# Ethernet1_PoE.net
KiCad netlist of a schematic drawn in Altium Designer
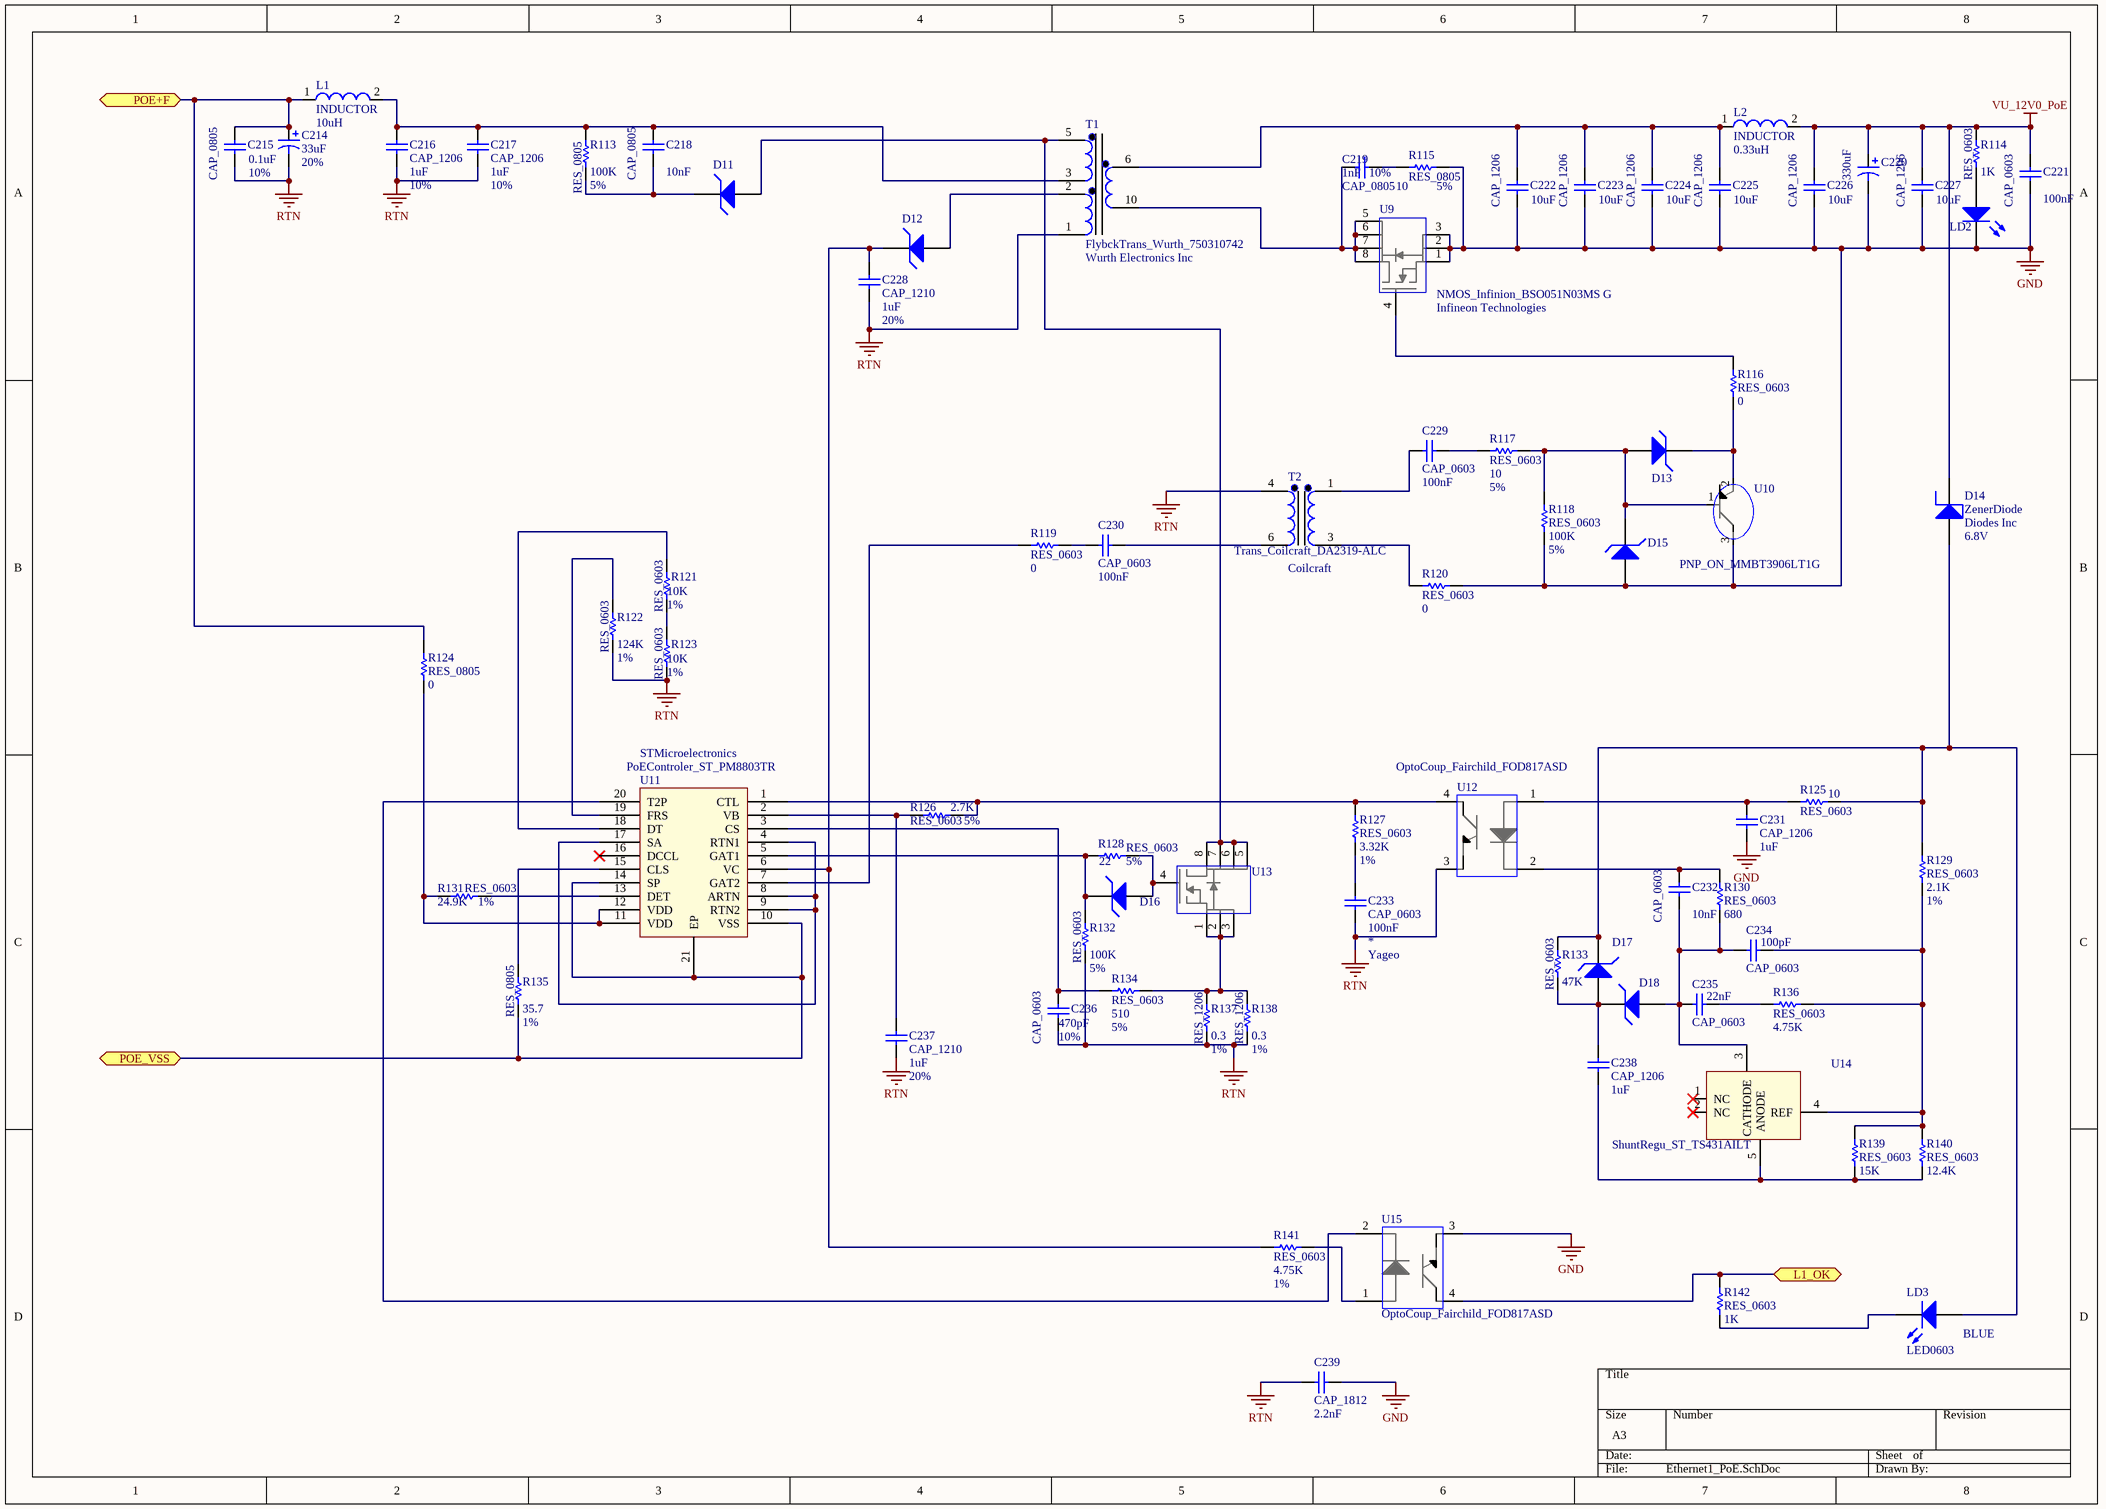
[diagram p0: Ethernet1_PoE.SchDoc]

(export (version "E")
  (design (tool "Eeschema 10.0.6"))
  (components
    (comp (ref "C214")
      (value "33uF")
      (footprint "CapPol_Al_EEE-2AA330P")
      (description "CAP ALUM 33UF 100V 20% SMD")
      (fields
        (field (name "TOLERANCE") "20%")
        (field (name "PART NUMBER") "EEE-2AA330P")
        (field (name "MANUFACTURER") "Panasonic Electronic Components")
      )
      (libsource (lib "COMRAD_Database") (part "Cap Pol1"))
    )
    (comp (ref "C215")
      (value "CAP_0805")
      (footprint "CAPC0805(2012)75_N")
      (description "CAP CER 0.1UF 100V 10% X7R 0805")
      (fields
        (field (name "ALTIUM_VALUE") "0.1uF")
        (field (name "TOLERANCE") "10%")
        (field (name "PART NUMBER") "C2012X7R2A104K")
        (field (name "MANUFACTURER") "TDK Corporation")
      )
      (libsource (lib "COMRAD_Database") (part "CAP_0805"))
    )
    (comp (ref "C216")
      (value "CAP_1206")
      (footprint "CAPC1206(3216)100_N")
      (description "CAP CER 1UF 100V 10% X7R 1206")
      (fields
        (field (name "ALTIUM_VALUE") "1uF")
        (field (name "TOLERANCE") "10%")
        (field (name "PART NUMBER") "C3216X7R2A105K")
        (field (name "MANUFACTURER") "TDK Corporation")
      )
      (libsource (lib "COMRAD_Database") (part "CAP_1206"))
    )
    (comp (ref "C217")
      (value "CAP_1206")
      (footprint "CAPC1206(3216)100_N")
      (description "CAP CER 1UF 100V 10% X7R 1206")
      (fields
        (field (name "ALTIUM_VALUE") "1uF")
        (field (name "TOLERANCE") "10%")
        (field (name "PART NUMBER") "C3216X7R2A105K")
        (field (name "MANUFACTURER") "TDK Corporation")
      )
      (libsource (lib "COMRAD_Database") (part "CAP_1206"))
    )
    (comp (ref "C218")
      (value "CAP_0805")
      (footprint "CAPC0805(2012)75_N")
      (description "CAP CER 10000PF 100V X7R 0805")
      (fields
        (field (name "ALTIUM_VALUE") "10nF")
        (field (name "PART NUMBER") "C2012X7R2A103K")
        (field (name "MANUFACTURER") "TDK Corporation")
      )
      (libsource (lib "COMRAD_Database") (part "CAP_0805"))
    )
    (comp (ref "C219")
      (value "CAP_0805")
      (footprint "CAPC0805(2012)75_N")
      (description "CAP CER 1000PF 100V 10% X7R 0805")
      (fields
        (field (name "ALTIUM_VALUE") "1nF")
        (field (name "TOLERANCE") "10%")
        (field (name "PART NUMBER") "101R15W102KV4T")
        (field (name "MANUFACTURER") "Johanson Dielectrics Inc")
      )
      (libsource (lib "COMRAD_Database") (part "CAP_0805"))
    )
    (comp (ref "C220")
      (value "330uF")
      (footprint "CapPol_Al_PCV1D331MCL2GS")
      (description "CAP ALUM 330UF 20V 20% SMD")
      (fields (field (name "PART NUMBER") "PCV1D331MCL2GS") (field (name "MANUFACTURER") "Nichicon"))
      (libsource (lib "COMRAD_Database") (part "Cap Pol1"))
    )
    (comp (ref "C221")
      (value "CAP_0603")
      (footprint "CAPC0603(1608)100_N:CAPC0603(1608)100_N")
      (description "CAP CER 0.1UF 50V Y5V 0603")
      (fields
        (field (name "ALTIUM_VALUE") "100nF")
        (field (name "PART NUMBER") "CC0603ZRY5V9BB104")
        (field (name "MANUFACTURER") "Yageo")
      )
      (libsource (lib "COMRAD_Database") (part "CAP_0603"))
    )
    (comp (ref "C222")
      (value "CAP_1206")
      (footprint "CAPC1206(3216)100_N")
      (description "CAP CER 10UF 25V Y5V 1206")
      (fields
        (field (name "ALTIUM_VALUE") "10uF")
        (field (name "PART NUMBER") "TMK316F106ZL-T")
        (field (name "MANUFACTURER") "Taiyo Yuden")
      )
      (libsource (lib "COMRAD_Database") (part "CAP_1206"))
    )
    (comp (ref "C223")
      (value "CAP_1206")
      (footprint "CAPC1206(3216)100_N")
      (description "CAP CER 10UF 25V Y5V 1206")
      (fields
        (field (name "ALTIUM_VALUE") "10uF")
        (field (name "PART NUMBER") "TMK316F106ZL-T")
        (field (name "MANUFACTURER") "Taiyo Yuden")
      )
      (libsource (lib "COMRAD_Database") (part "CAP_1206"))
    )
    (comp (ref "C224")
      (value "CAP_1206")
      (footprint "CAPC1206(3216)100_N")
      (description "CAP CER 10UF 25V Y5V 1206")
      (fields
        (field (name "ALTIUM_VALUE") "10uF")
        (field (name "PART NUMBER") "TMK316F106ZL-T")
        (field (name "MANUFACTURER") "Taiyo Yuden")
      )
      (libsource (lib "COMRAD_Database") (part "CAP_1206"))
    )
    (comp (ref "C225")
      (value "CAP_1206")
      (footprint "CAPC1206(3216)100_N")
      (description "CAP CER 10UF 25V Y5V 1206")
      (fields
        (field (name "ALTIUM_VALUE") "10uF")
        (field (name "PART NUMBER") "TMK316F106ZL-T")
        (field (name "MANUFACTURER") "Taiyo Yuden")
      )
      (libsource (lib "COMRAD_Database") (part "CAP_1206"))
    )
    (comp (ref "C226")
      (value "CAP_1206")
      (footprint "CAPC1206(3216)100_N")
      (description "CAP CER 10UF 25V Y5V 1206")
      (fields
        (field (name "ALTIUM_VALUE") "10uF")
        (field (name "PART NUMBER") "TMK316F106ZL-T")
        (field (name "MANUFACTURER") "Taiyo Yuden")
      )
      (libsource (lib "COMRAD_Database") (part "CAP_1206"))
    )
    (comp (ref "C227")
      (value "CAP_1206")
      (footprint "CAPC1206(3216)100_N")
      (description "CAP CER 10UF 25V Y5V 1206")
      (fields
        (field (name "ALTIUM_VALUE") "10uF")
        (field (name "PART NUMBER") "TMK316F106ZL-T")
        (field (name "MANUFACTURER") "Taiyo Yuden")
      )
      (libsource (lib "COMRAD_Database") (part "CAP_1206"))
    )
    (comp (ref "C228")
      (value "CAP_1210")
      (footprint "CAPC1210(3225)100_N")
      (description "CAP CER 1UF 16V 20% X7R 1210")
      (fields
        (field (name "ALTIUM_VALUE") "1uF")
        (field (name "TOLERANCE") "20%")
        (field (name "PART NUMBER") "160X41W105MV4E")
        (field (name "MANUFACTURER") "Johanson Dielectrics Inc")
      )
      (libsource (lib "COMRAD_Database") (part "CAP_1210"))
    )
    (comp (ref "C229")
      (value "CAP_0603")
      (footprint "CAPC0603(1608)100_N:CAPC0603(1608)100_N")
      (description "CAP CER 0.1UF 50V Y5V 0603")
      (fields
        (field (name "ALTIUM_VALUE") "100nF")
        (field (name "PART NUMBER") "CC0603ZRY5V9BB104")
        (field (name "MANUFACTURER") "Yageo")
      )
      (libsource (lib "COMRAD_Database") (part "CAP_0603"))
    )
    (comp (ref "C230")
      (value "CAP_0603")
      (footprint "CAPC0603(1608)100_N:CAPC0603(1608)100_N")
      (description "CAP CER 0.1UF 50V Y5V 0603")
      (fields
        (field (name "ALTIUM_VALUE") "100nF")
        (field (name "PART NUMBER") "CC0603ZRY5V9BB104")
        (field (name "MANUFACTURER") "Yageo")
      )
      (libsource (lib "COMRAD_Database") (part "CAP_0603"))
    )
    (comp (ref "C231")
      (value "CAP_1206")
      (footprint "CAPC1206(3216)100_N")
      (description "CAP CER 1UF 100V 10% X7R 1206")
      (fields
        (field (name "ALTIUM_VALUE") "1uF")
        (field (name "PART NUMBER") "C3216X7R2A105K")
        (field (name "MANUFACTURER") "TDK Corporation")
      )
      (libsource (lib "COMRAD_Database") (part "CAP_1206"))
    )
    (comp (ref "C232")
      (value "CAP_0603")
      (footprint "CAPC0603(1608)100_N:CAPC0603(1608)100_N")
      (description "CAP CER 10000PF 50V 10% X7R 0603")
      (fields
        (field (name "ALTIUM_VALUE") "10nF")
        (field (name "PART NUMBER") "C0603C103K5RACTU")
        (field (name "MANUFACTURER") "Kemet")
      )
      (libsource (lib "COMRAD_Database") (part "CAP_0603"))
    )
    (comp (ref "C233")
      (value "CAP_0603")
      (footprint "CAPC0603(1608)100_N:CAPC0603(1608)100_N")
      (description "CAP CER 0.1UF 50V Y5V 0603")
      (fields
        (field (name "ALTIUM_VALUE") "100nF")
        (field (name "TOLERANCE") "*")
        (field (name "PART NUMBER") "CC0603ZRY5V9BB104")
        (field (name "MANUFACTURER") "Yageo")
      )
      (libsource (lib "COMRAD_Database") (part "CAP_0603"))
    )
    (comp (ref "C234")
      (value "CAP_0603")
      (footprint "CAPC0603(1608)100_N:CAPC0603(1608)100_N")
      (description "CAP CER 100PF 50V 5% NP0 0603")
      (fields
        (field (name "ALTIUM_VALUE") "100pF")
        (field (name "PART NUMBER") "C0603C101J5GACTU")
        (field (name "MANUFACTURER") "Kemet")
      )
      (libsource (lib "COMRAD_Database") (part "CAP_0603"))
    )
    (comp (ref "C235")
      (value "CAP_0603")
      (footprint "CAPC0603(1608)100_N:CAPC0603(1608)100_N")
      (description "CAP CER 0.022UF 50V 10% X7R 0603")
      (fields
        (field (name "ALTIUM_VALUE") "22nF")
        (field (name "PART NUMBER") "C0603C223K5RACTU")
        (field (name "MANUFACTURER") "Kemet")
      )
      (libsource (lib "COMRAD_Database") (part "CAP_0603"))
    )
    (comp (ref "C236")
      (value "CAP_0603")
      (footprint "CAPC0603(1608)100_N:CAPC0603(1608)100_N")
      (description "CAP CER 470PF 50V 10% X7R 0603")
      (fields
        (field (name "ALTIUM_VALUE") "470pF")
        (field (name "TOLERANCE") "10%")
        (field (name "PART NUMBER") "CC0603KRX7R9BB471")
        (field (name "MANUFACTURER") "Yageo")
      )
      (libsource (lib "COMRAD_Database") (part "CAP_0603"))
    )
    (comp (ref "C237")
      (value "CAP_1210")
      (footprint "CAPC1210(3225)100_N")
      (description "CAP CER 1UF 16V 20% X7R 1210")
      (fields
        (field (name "ALTIUM_VALUE") "1uF")
        (field (name "TOLERANCE") "20%")
        (field (name "PART NUMBER") "160X41W105MV4E")
        (field (name "MANUFACTURER") "Johanson Dielectrics Inc")
      )
      (libsource (lib "COMRAD_Database") (part "CAP_1210"))
    )
    (comp (ref "C238")
      (value "CAP_1206")
      (footprint "CAPC1206(3216)100_N")
      (description "CAP CER 1UF 100V 10% X7R 1206")
      (fields
        (field (name "ALTIUM_VALUE") "1uF")
        (field (name "PART NUMBER") "C3216X7R2A105K")
        (field (name "MANUFACTURER") "TDK Corporation")
      )
      (libsource (lib "COMRAD_Database") (part "CAP_1206"))
    )
    (comp (ref "C239")
      (value "CAP_1812")
      (footprint "CAPC1812(4532)250_N")
      (description "CAP CER 2200PF 2KV 10% X7R 1812")
      (fields
        (field (name "ALTIUM_VALUE") "2.2nF")
        (field (name "PART NUMBER") "C1812C222KGRACTU")
        (field (name "MANUFACTURER") "Kemet")
      )
      (libsource (lib "COMRAD_Database") (part "CAP_1812"))
    )
    (comp (ref "D11")
      (value "Shottky Diode")
      (footprint "SchottlyDiode_STPS2H100A_SMA")
      (description "DIODE SCHOTTKY PWR 100V 2A SMA")
      (fields (field (name "PART NUMBER") "STPS2H100A") (field (name "MANUFACTURER") "STMicroelectronics"))
      (libsource (lib "COMRAD_Database") (part "ShottkyDiode"))
    )
    (comp (ref "D12")
      (value "Shottky Diode")
      (footprint "SchottkyDiode_BAT46JFILM")
      (description "IC DIODE SCHOTTKY SS SOD-323")
      (fields (field (name "PART NUMBER") "BAT46JFILM") (field (name "MANUFACTURER") "STMicroelectronics"))
      (libsource (lib "COMRAD_Database") (part "ShottkyDiode"))
    )
    (comp (ref "D13")
      (value "Shottky Diode")
      (footprint "SchottkyDiode_BAT46JFILM")
      (description "IC DIODE SCHOTTKY SS SOD-323")
      (fields (field (name "PART NUMBER") "BAT46JFILM") (field (name "MANUFACTURER") "STMicroelectronics"))
      (libsource (lib "COMRAD_Database") (part "ShottkyDiode"))
    )
    (comp (ref "D14")
      (value "ZenerDiode")
      (footprint "ZenerDiode_DDZ6V8CSF-7_2-PIN")
      (description "DIODE ZENER 6.84V 500MW SOD323F")
      (fields
        (field (name "PART NUMBER") "DDZ6V8CSF-7")
        (field (name "MANUFACTURER") "Diodes Inc")
        (field (name "ALTIUM_VALUE") "6.8V")
      )
      (libsource (lib "COMRAD_Database") (part "ZenerDiode"))
    )
    (comp (ref "D15")
      (value "Shottky Diode")
      (footprint "SchottkyDiode_BAT46JFILM")
      (description "IC DIODE SCHOTTKY SS SOD-323")
      (fields (field (name "PART NUMBER") "BAT46JFILM") (field (name "MANUFACTURER") "STMicroelectronics"))
      (libsource (lib "COMRAD_Database") (part "ShottkyDiode"))
    )
    (comp (ref "D16")
      (value "Shottky Diode")
      (footprint "SchottkyDiode_BAT46JFILM")
      (description "IC DIODE SCHOTTKY SS SOD-323")
      (fields (field (name "PART NUMBER") "BAT46JFILM") (field (name "MANUFACTURER") "STMicroelectronics"))
      (libsource (lib "COMRAD_Database") (part "ShottkyDiode"))
    )
    (comp (ref "D17")
      (value "Shottky Diode")
      (footprint "SchottkyDiode_BAT46JFILM")
      (description "IC DIODE SCHOTTKY SS SOD-323")
      (fields (field (name "PART NUMBER") "BAT46JFILM") (field (name "MANUFACTURER") "STMicroelectronics"))
      (libsource (lib "COMRAD_Database") (part "ShottkyDiode"))
    )
    (comp (ref "D18")
      (value "Shottky Diode")
      (footprint "SchottkyDiode_BAT46JFILM")
      (description "IC DIODE SCHOTTKY SS SOD-323")
      (fields (field (name "PART NUMBER") "BAT46JFILM") (field (name "MANUFACTURER") "STMicroelectronics"))
      (libsource (lib "COMRAD_Database") (part "ShottkyDiode"))
    )
    (comp (ref "L1")
      (value "INDUCTOR")
      (footprint "Inductor_MSS7341-103MLB_2-PIN")
      (description "INDUCTOR, 10uH,DCR 0.038, CURRENT 1.64A")
      (fields
        (field (name "ALTIUM_VALUE") "10uH")
        (field (name "PART NUMBER") "MSS7341-103MLB")
        (field (name "MANUFACTURER") "Coilcraft")
      )
      (libsource (lib "COMRAD_Database") (part "SYM-0029-00001-1"))
    )
    (comp (ref "L2")
      (value "INDUCTOR")
      (footprint "Inductor_DO1813H-181MLB_2-PINS")
      (description "INDUCTOR, 0.33uH,DCR 0.004, CURRENT 10A")
      (fields
        (field (name "ALTIUM_VALUE") "0.33uH")
        (field (name "PART NUMBER") "DO1813H-181MLB")
        (field (name "MANUFACTURER") "Coilcraft")
      )
      (libsource (lib "COMRAD_Database") (part "SYM-0029-00001-1"))
    )
    (comp (ref "LD2")
      (value "LED0805")
      (footprint "LED0805(2012):LED0805(2012)")
      (description "LED GREEN CLEAR THIN 0805 SMD")
      (fields (field (name "PART NUMBER") "LTST-C171GKT") (field (name "MANUFACTURER") "Lite-On Inc"))
      (libsource (lib "COMRAD_Database") (part "LED0805"))
    )
    (comp (ref "LD3")
      (value "LED0603")
      (footprint "LED0603(1608):LED0603(1608)")
      (description "Blue, SMD, 0603 Hi Brite")
      (fields
        (field (name "PART NUMBER") "UT-692NB")
        (field (name "MANUFACTURER") "LightComp LED")
        (field (name "ALTIUM_VALUE") "BLUE")
      )
      (libsource (lib "COMRAD_Database") (part "LED0603"))
    )
    (comp (ref "R113")
      (value "RES_0805")
      (footprint "RESC0805(2012)_N")
      (description "RES 100K OHM 1/8W 5% 0805 SMD")
      (fields
        (field (name "ALTIUM_VALUE") "100K")
        (field (name "TOLERANCE") "5%")
        (field (name "PART NUMBER") "CRCW0805100KJNEA")
        (field (name "MANUFACTURER") "Vishay Dale")
      )
      (libsource (lib "COMRAD_Database") (part "RES_0805"))
    )
    (comp (ref "R114")
      (value "RES_0603")
      (footprint "RESC0603(1608)_N")
      (description "RES 1.0K OHM 1/10W 5% 0603 SMD")
      (fields
        (field (name "ALTIUM_VALUE") "1K")
        (field (name "PART NUMBER") "ERJ-3GEYJ102V")
        (field (name "MANUFACTURER") "Panasonic Electronic Components")
      )
      (libsource (lib "COMRAD_Database") (part "RES_0603"))
    )
    (comp (ref "R115")
      (value "RES_0805")
      (footprint "RESC0805(2012)_N")
      (description "RES 10 OHM 1/8W 5% 0805 SMD")
      (fields
        (field (name "ALTIUM_VALUE") "10")
        (field (name "TOLERANCE") "5%")
        (field (name "PART NUMBER") "CRCW080510R0JNEA")
        (field (name "MANUFACTURER") "Vishay Dale")
      )
      (libsource (lib "COMRAD_Database") (part "RES_0805"))
    )
    (comp (ref "R116")
      (value "RES_0603")
      (footprint "RESC0603(1608)_N")
      (description "RES 0.0 OHM 1/10W 0603 SMD")
      (fields
        (field (name "ALTIUM_VALUE") "0")
        (field (name "PART NUMBER") "ERJ-3GEY0R00V")
        (field (name "MANUFACTURER") "Panasonic Electronic Components")
      )
      (libsource (lib "COMRAD_Database") (part "RES_0603"))
    )
    (comp (ref "R117")
      (value "RES_0603")
      (footprint "RESC0603(1608)_N")
      (description "RES 10 OHM 1/10W 5% 0603 SMD")
      (fields
        (field (name "ALTIUM_VALUE") "10")
        (field (name "TOLERANCE") "5%")
        (field (name "PART NUMBER") "ERJ-3GEYJ100V")
        (field (name "MANUFACTURER") "Panasonic Electronic Components")
      )
      (libsource (lib "COMRAD_Database") (part "RES_0603"))
    )
    (comp (ref "R118")
      (value "RES_0603")
      (footprint "RESC0603(1608)_N")
      (description "RES 100K OHM 1/10W 5% 0603 SMD")
      (fields
        (field (name "ALTIUM_VALUE") "100K")
        (field (name "TOLERANCE") "5%")
        (field (name "PART NUMBER") "ERJ-3GEYJ104V")
        (field (name "MANUFACTURER") "Panasonic Electronic Components")
      )
      (libsource (lib "COMRAD_Database") (part "RES_0603"))
    )
    (comp (ref "R119")
      (value "RES_0603")
      (footprint "RESC0603(1608)_N")
      (description "RES 0.0 OHM 1/10W 0603 SMD")
      (fields
        (field (name "ALTIUM_VALUE") "0")
        (field (name "PART NUMBER") "ERJ-3GEY0R00V")
        (field (name "MANUFACTURER") "Panasonic Electronic Components")
      )
      (libsource (lib "COMRAD_Database") (part "RES_0603"))
    )
    (comp (ref "R120")
      (value "RES_0603")
      (footprint "RESC0603(1608)_N")
      (description "RES 0.0 OHM 1/10W 0603 SMD")
      (fields
        (field (name "ALTIUM_VALUE") "0")
        (field (name "PART NUMBER") "ERJ-3GEY0R00V")
        (field (name "MANUFACTURER") "Panasonic Electronic Components")
      )
      (libsource (lib "COMRAD_Database") (part "RES_0603"))
    )
    (comp (ref "R121")
      (value "RES_0603")
      (footprint "RESC0603(1608)_N")
      (description "RES 10.0K OHM 1/10W 1% 0603 SMD")
      (fields
        (field (name "ALTIUM_VALUE") "10K")
        (field (name "TOLERANCE") "1%")
        (field (name "PART NUMBER") "ERJ-3EKF1002V")
        (field (name "MANUFACTURER") "Panasonic Electronics Components")
      )
      (libsource (lib "COMRAD_Database") (part "RES_0603"))
    )
    (comp (ref "R122")
      (value "RES_0603")
      (footprint "RESC0603(1608)_N")
      (description "RES 124K OHM 1/10W 1% 0603 SMD")
      (fields
        (field (name "ALTIUM_VALUE") "124K")
        (field (name "TOLERANCE") "1%")
        (field (name "PART NUMBER") "ERJ-3EKF1243V")
        (field (name "MANUFACTURER") "Panasonic Electronic Components")
      )
      (libsource (lib "COMRAD_Database") (part "RES_0603"))
    )
    (comp (ref "R123")
      (value "RES_0603")
      (footprint "RESC0603(1608)_N")
      (description "RES 10.0K OHM 1/10W 1% 0603 SMD")
      (fields
        (field (name "ALTIUM_VALUE") "10K")
        (field (name "TOLERANCE") "1%")
        (field (name "PART NUMBER") "ERJ-3EKF1002V")
        (field (name "MANUFACTURER") "Panasonic Electronics Components")
      )
      (libsource (lib "COMRAD_Database") (part "RES_0603"))
    )
    (comp (ref "R124")
      (value "RES_0805")
      (footprint "RESC0805(2012)_N")
      (description "RES 0.0 OHM 1/8W 0805 SMD")
      (fields
        (field (name "ALTIUM_VALUE") "0")
        (field (name "PART NUMBER") "CRCW08050000Z0EA")
        (field (name "MANUFACTURER") "Vishay Dale")
      )
      (libsource (lib "COMRAD_Database") (part "RES_0805"))
    )
    (comp (ref "R125")
      (value "RES_0603")
      (footprint "RESC0603(1608)_N")
      (description "RES 10 OHM 1/10W 5% 0603 SMD")
      (fields
        (field (name "ALTIUM_VALUE") "10")
        (field (name "PART NUMBER") "ERJ-3GEYJ100V")
        (field (name "MANUFACTURER") "Panasonic Electronic Components")
      )
      (libsource (lib "COMRAD_Database") (part "RES_0603"))
    )
    (comp (ref "R126")
      (value "RES_0603")
      (footprint "RESC0603(1608)_N")
      (description "RES 2.7K OHM 1/10W 5% 0603 SMD")
      (fields
        (field (name "ALTIUM_VALUE") "2.7K")
        (field (name "TOLERANCE") "5%")
        (field (name "PART NUMBER") "ERJ-3GEYJ272V")
        (field (name "MANUFACTURER") "Panasonic Electronic Components")
      )
      (libsource (lib "COMRAD_Database") (part "RES_0603"))
    )
    (comp (ref "R127")
      (value "RES_0603")
      (footprint "RESC0603(1608)_N")
      (description "RES 3.32K OHM 1/10W 1% 0603 SMD")
      (fields
        (field (name "ALTIUM_VALUE") "3.32K")
        (field (name "TOLERANCE") "1%")
        (field (name "PART NUMBER") "ERJ-3EKF3321V")
        (field (name "MANUFACTURER") "Panasonic Electronic Components")
      )
      (libsource (lib "COMRAD_Database") (part "RES_0603"))
    )
    (comp (ref "R128")
      (value "RES_0603")
      (footprint "RESC0603(1608)_N")
      (description "RES 22 OHM 1/10W 5% 0603 SMD")
      (fields
        (field (name "ALTIUM_VALUE") "22")
        (field (name "TOLERANCE") "5%")
        (field (name "PART NUMBER") "ERJ-3GEYJ220V")
        (field (name "MANUFACTURER") "Panasonic Electronic Components")
      )
      (libsource (lib "COMRAD_Database") (part "RES_0603"))
    )
    (comp (ref "R129")
      (value "RES_0603")
      (footprint "RESC0603(1608)_N")
      (description "RES 2.10K OHM 1/10W 1% 0603 SMD")
      (fields
        (field (name "ALTIUM_VALUE") "2.1K")
        (field (name "TOLERANCE") "1%")
        (field (name "PART NUMBER") "ERJ-3EKF2101V")
        (field (name "MANUFACTURER") "Panasonic Electronic Components")
      )
      (libsource (lib "COMRAD_Database") (part "RES_0603"))
    )
    (comp (ref "R130")
      (value "RES_0603")
      (footprint "RESC0603(1608)_N")
      (description "RES 680 OHM 1/10W 5% 0603 SMD")
      (fields
        (field (name "ALTIUM_VALUE") "680")
        (field (name "PART NUMBER") "ERJ-3GEYJ681V")
        (field (name "MANUFACTURER") "Panasonic Electronic Components")
      )
      (libsource (lib "COMRAD_Database") (part "RES_0603"))
    )
    (comp (ref "R131")
      (value "RES_0603")
      (footprint "RESC0603(1608)_N")
      (description "RES 24.9K OHM 1/10W 1% 0603 SMD")
      (fields
        (field (name "ALTIUM_VALUE") "24.9K")
        (field (name "TOLERANCE") "1%")
        (field (name "PART NUMBER") "ERJ-3EKF2492V")
        (field (name "MANUFACTURER") "Panasonic Electronics Components")
      )
      (libsource (lib "COMRAD_Database") (part "RES_0603"))
    )
    (comp (ref "R132")
      (value "RES_0603")
      (footprint "RESC0603(1608)_N")
      (description "RES 100K OHM 1/10W 5% 0603 SMD")
      (fields
        (field (name "ALTIUM_VALUE") "100K")
        (field (name "TOLERANCE") "5%")
        (field (name "PART NUMBER") "ERJ-3GEYJ104V")
        (field (name "MANUFACTURER") "Panasonic Electronic Components")
      )
      (libsource (lib "COMRAD_Database") (part "RES_0603"))
    )
    (comp (ref "R133")
      (value "RES_0603")
      (footprint "RESC0603(1608)_N")
      (description "RES 47K OHM 1/10W 5% 0603 SMD")
      (fields
        (field (name "ALTIUM_VALUE") "47K")
        (field (name "PART NUMBER") "ERJ-3GEYJ473V")
        (field (name "MANUFACTURER") "Panasonic Electronic Components")
      )
      (libsource (lib "COMRAD_Database") (part "RES_0603"))
    )
    (comp (ref "R134")
      (value "RES_0603")
      (footprint "RESC0603(1608)_N")
      (description "RES 510 OHM 1/10W 5% 0603 SMD")
      (fields
        (field (name "ALTIUM_VALUE") "510")
        (field (name "TOLERANCE") "5%")
        (field (name "PART NUMBER") "ERJ-3GEYJ511V")
        (field (name "MANUFACTURER") "Panasonic Electronic Components")
      )
      (libsource (lib "COMRAD_Database") (part "RES_0603"))
    )
    (comp (ref "R135")
      (value "RES_0805")
      (footprint "RESC0805(2012)_N")
      (description "RES 35.7 OHM 1/8W 1% 0805 SMD")
      (fields
        (field (name "ALTIUM_VALUE") "35.7")
        (field (name "TOLERANCE") "1%")
        (field (name "PART NUMBER") "CRCW080535R7FKEA")
        (field (name "MANUFACTURER") "Vishay Dale")
      )
      (libsource (lib "COMRAD_Database") (part "RES_0805"))
    )
    (comp (ref "R136")
      (value "RES_0603")
      (footprint "RESC0603(1608)_N")
      (description "RES 4.75K OHM 1/10W 1% 0603 SMD")
      (fields
        (field (name "ALTIUM_VALUE") "4.75K")
        (field (name "PART NUMBER") "ERJ-3EKF4751V")
        (field (name "MANUFACTURER") "Panasonic Electronic Components")
      )
      (libsource (lib "COMRAD_Database") (part "RES_0603"))
    )
    (comp (ref "R137")
      (value "RES_1206")
      (footprint "RESC1206(3216)_N")
      (description "RES 0.3OHM 1/2W 1% 1206 SMD")
      (fields
        (field (name "ALTIUM_VALUE") "0.3")
        (field (name "TOLERANCE") "1%")
        (field (name "PART NUMBER") "CSR1206FKR300")
        (field (name "MANUFACTURER") "Stackpole Electronics Inc")
      )
      (libsource (lib "COMRAD_Database") (part "RES_1206"))
    )
    (comp (ref "R138")
      (value "RES_1206")
      (footprint "RESC1206(3216)_N")
      (description "RES 0.3OHM 1/2W 1% 1206 SMD")
      (fields
        (field (name "ALTIUM_VALUE") "0.3")
        (field (name "TOLERANCE") "1%")
        (field (name "PART NUMBER") "CSR1206FKR300")
        (field (name "MANUFACTURER") "Stackpole Electronics Inc")
      )
      (libsource (lib "COMRAD_Database") (part "RES_1206"))
    )
    (comp (ref "R139")
      (value "RES_0603")
      (footprint "RESC0603(1608)_N")
      (description "RES 15K OHM 1/10W 5% 0603 SMD")
      (fields
        (field (name "ALTIUM_VALUE") "15K")
        (field (name "PART NUMBER") "ERJ-3GEYJ153V")
        (field (name "MANUFACTURER") "Panasonic Electronic Components")
      )
      (libsource (lib "COMRAD_Database") (part "RES_0603"))
    )
    (comp (ref "R140")
      (value "RES_0603")
      (footprint "RESC0603(1608)_N")
      (description "RES 12.4K OHM 1/8W 1% 0603 SMD")
      (fields
        (field (name "ALTIUM_VALUE") "12.4K")
        (field (name "PART NUMBER") "RNCP0603FTD12K4")
        (field (name "MANUFACTURER") "Stackpole Electronics Inc")
      )
      (libsource (lib "COMRAD_Database") (part "RES_0603"))
    )
    (comp (ref "R141")
      (value "RES_0603")
      (footprint "RESC0603(1608)_N")
      (description "RES 4.75K OHM 1/10W 1% 0603 SMD")
      (fields
        (field (name "ALTIUM_VALUE") "4.75K")
        (field (name "TOLERANCE") "1%")
        (field (name "PART NUMBER") "ERJ-3EKF4751V")
        (field (name "MANUFACTURER") "Panasonic Electronic Components")
      )
      (libsource (lib "COMRAD_Database") (part "RES_0603"))
    )
    (comp (ref "R142")
      (value "RES_0603")
      (footprint "RESC0603(1608)_N")
      (description "RES 1.00K OHM 1/10W 1% 0603 SMD")
      (fields
        (field (name "ALTIUM_VALUE") "1K")
        (field (name "PART NUMBER") "ERJ-3EKF1001V")
        (field (name "MANUFACTURER") "Panasonic Electronics Components")
      )
      (libsource (lib "COMRAD_Database") (part "RES_0603"))
    )
    (comp (ref "T1")
      (value "FlybckTrans_Wurth_750310742")
      (footprint "FlybckTrans_Wurth_750310742_10PinSMD")
      (description "TRANS FLYBACK POE+ 38UH SMD")
      (fields (field (name "PART NUMBER") "750310742") (field (name "MANUFACTURER") "Wurth Electronics Inc"))
      (libsource (lib "COMRAD_Database") (part "FlybckTrans_Wurth_750310742"))
    )
    (comp (ref "T2")
      (value "Trans_Coilcraft_DA2319-ALC")
      (footprint "Trans_Coilcraft_DA2319-ALC_SOP-6")
      (description "SMT Gate Drive Transmorfer")
      (fields (field (name "PART NUMBER") "DA2319-ALC") (field (name "MANUFACTURER") "Coilcraft"))
      (libsource (lib "COMRAD_Database") (part "Trans_Coilcraft_DA2319-ALC"))
    )
    (comp (ref "U9")
      (value "NMOS_Infinion_BSO051N03MS G")
      (footprint "NMOS_Infinion_BSO051N03MS G_PG-DSO-8")
      (description "MOSFET N-CH 30V 14A DSO-8")
      (fields
        (field (name "PART NUMBER") "BSO051N03MS G")
        (field (name "MANUFACTURER") "Infineon Technologies")
      )
      (libsource (lib "COMRAD_Database") (part "NMOS_Infinion_BSO051N03MS G"))
    )
    (comp (ref "U10")
      (value "PNP_ON_MMBT3906LT1G")
      (footprint "MMBT3906LT1G_SOT23-3")
      (description "TRANS GP SS PNP 40V SOT23")
      (fields (field (name "PART NUMBER") "MMBT3906LT1G") (field (name "MANUFACTURER") "ON Semiconductor"))
      (libsource (lib "COMRAD_Database") (part "PNP_ON_MMBT3906LT1G"))
    )
    (comp (ref "U11")
      (value "PoEControler_ST_PM8803TR")
      (footprint "PoEControler_ST_PM8803TR_HTSSOP20")
      (description "IC POE-PD/PWM CTLR 20-HTSSOP")
      (fields (field (name "PART NUMBER") "PM8803TR") (field (name "MANUFACTURER") "STMicroelectronics"))
      (libsource (lib "COMRAD_Database") (part "PoEControler_ST_PM8803TR"))
    )
    (comp (ref "U12")
      (value "OptoCoup_Fairchild_FOD817ASD")
      (footprint "OptoCoup_Fairchild_FOD817ASD_4-SMD")
      (description "OPTOCOUPLER PHOTOTRANS OUT 4-SMD")
      (fields
        (field (name "PART NUMBER") "FOD817ASD")
        (field (name "MANUFACTURER") "Fairchild Optoelectronics Group")
      )
      (libsource (lib "COMRAD_Database") (part "OptoCoup_Fairchild_FOD817ASD"))
    )
    (comp (ref "U13")
      (value "NMOS_Vishay_SI4848DY-T1-E3")
      (footprint "NMOS_Vishay_SI4848DY-T1-E3_SO-8")
      (description "MOSFET N-CH 150V 2.7A 8-SOIC")
      (fields (field (name "PART NUMBER") "SI4848DY-T1-E3") (field (name "MANUFACTURER") "Vishay Siliconix"))
      (libsource (lib "COMRAD_Database") (part "NMOS_Vishay_SI4848DY-T1-E3"))
    )
    (comp (ref "U14")
      (value "ShuntRegu_ST_TS431AILT")
      (footprint "ShuntRegu_ST_TS431AILT_SOT23-5")
      (description "IC VREF SHUNT PREC ADJ SOT-23-5")
      (fields (field (name "PART NUMBER") "TS431AILT") (field (name "MANUFACTURER") "STMicroelectronics"))
      (libsource (lib "COMRAD_Database") (part "ShuntRegu_ST_TS431AILT"))
    )
    (comp (ref "U15")
      (value "OptoCoup_Fairchild_FOD817ASD")
      (footprint "OptoCoup_Fairchild_FOD817ASD_4-SMD")
      (description "OPTOCOUPLER PHOTOTRANS OUT 4-SMD")
      (fields
        (field (name "PART NUMBER") "FOD817ASD")
        (field (name "MANUFACTURER") "Fairchild Optoelectronics Group")
      )
      (libsource (lib "") (part "OptoCoup_Fairchild_FOD817ASD_1"))
    )
  )
  (nets
    (net (code "1") (name "/L1_OK") (class "Default")
      (node (ref "R142") (pin "2") (pinfunction "2_2") (pintype "passive"))
      (node (ref "U15") (pin "4") (pinfunction "Collector_4") (pintype "passive"))
    )
    (net (code "2") (name "/POE+F") (class "Default")
      (node (ref "C214") (pin "1") (pinfunction "1_1") (pintype "passive"))
      (node (ref "C215") (pin "2") (pinfunction "2_2") (pintype "passive"))
      (node (ref "L1") (pin "1") (pinfunction "1_1") (pintype "passive"))
      (node (ref "R124") (pin "2") (pinfunction "2_2") (pintype "passive"))
    )
    (net (code "3") (name "/POE_VSS") (class "Default")
      (node (ref "R135") (pin "1") (pinfunction "1_1") (pintype "passive"))
      (node (ref "U11") (pin "10") (pinfunction "VSS_10") (pintype "passive"))
      (node (ref "U11") (pin "14") (pinfunction "SP_14") (pintype "passive"))
      (node (ref "U11") (pin "21") (pinfunction "EP_21") (pintype "passive"))
    )
    (net (code "4") (name "GND") (class "Default")
      (node (ref "C220") (pin "2") (pinfunction "2_2") (pintype "passive"))
      (node (ref "C221") (pin "1") (pinfunction "1_1") (pintype "passive"))
      (node (ref "C222") (pin "1") (pinfunction "1_1") (pintype "passive"))
      (node (ref "C223") (pin "1") (pinfunction "1_1") (pintype "passive"))
      (node (ref "C224") (pin "1") (pinfunction "1_1") (pintype "passive"))
      (node (ref "C225") (pin "1") (pinfunction "1_1") (pintype "passive"))
      (node (ref "C226") (pin "1") (pinfunction "1_1") (pintype "passive"))
      (node (ref "C227") (pin "1") (pinfunction "1_1") (pintype "passive"))
      (node (ref "C231") (pin "1") (pinfunction "1_1") (pintype "passive"))
      (node (ref "C239") (pin "2") (pinfunction "2_2") (pintype "passive"))
      (node (ref "D15") (pin "2") (pinfunction "A_2") (pintype "passive"))
      (node (ref "LD2") (pin "1") (pinfunction "K_1") (pintype "passive"))
      (node (ref "R115") (pin "2") (pinfunction "2_2") (pintype "passive"))
      (node (ref "R118") (pin "1") (pinfunction "1_1") (pintype "passive"))
      (node (ref "R120") (pin "2") (pinfunction "2_2") (pintype "passive"))
      (node (ref "U10") (pin "3") (pintype "passive"))
      (node (ref "U15") (pin "3") (pinfunction "Emitter_3") (pintype "passive"))
      (node (ref "U9") (pin "1") (pintype "passive"))
      (node (ref "U9") (pin "2") (pintype "passive"))
      (node (ref "U9") (pin "3") (pintype "passive"))
    )
    (net (code "5") (name "Net-(C216-Pad2)") (class "Default")
      (node (ref "C216") (pin "2") (pinfunction "2_2") (pintype "passive"))
      (node (ref "C217") (pin "2") (pinfunction "2_2") (pintype "passive"))
      (node (ref "C218") (pin "2") (pinfunction "2_2") (pintype "passive"))
      (node (ref "L1") (pin "2") (pinfunction "2_2") (pintype "passive"))
      (node (ref "R113") (pin "2") (pinfunction "2_2") (pintype "passive"))
      (node (ref "T1") (pin "3") (pintype "passive"))
    )
    (net (code "6") (name "Net-(C219-Pad1)") (class "Default")
      (node (ref "C219") (pin "1") (pinfunction "1_1") (pintype "passive"))
      (node (ref "T1") (pin "10") (pintype "passive"))
      (node (ref "U9") (pin "5") (pintype "passive"))
      (node (ref "U9") (pin "6") (pintype "passive"))
      (node (ref "U9") (pin "7") (pintype "passive"))
      (node (ref "U9") (pin "8") (pintype "passive"))
    )
    (net (code "7") (name "Net-(C219-Pad2)") (class "Default")
      (node (ref "C219") (pin "2") (pinfunction "2_2") (pintype "passive"))
      (node (ref "R115") (pin "1") (pinfunction "1_1") (pintype "passive"))
    )
    (net (code "8") (name "Net-(C222-Pad2)") (class "Default")
      (node (ref "C222") (pin "2") (pinfunction "2_2") (pintype "passive"))
      (node (ref "C223") (pin "2") (pinfunction "2_2") (pintype "passive"))
      (node (ref "C224") (pin "2") (pinfunction "2_2") (pintype "passive"))
      (node (ref "C225") (pin "2") (pinfunction "2_2") (pintype "passive"))
      (node (ref "L2") (pin "1") (pinfunction "1_1") (pintype "passive"))
      (node (ref "T1") (pin "6") (pintype "passive"))
    )
    (net (code "9") (name "Net-(C229-Pad1)") (class "Default")
      (node (ref "C229") (pin "1") (pinfunction "1_1") (pintype "passive"))
      (node (ref "T2") (pin "1") (pintype "passive"))
    )
    (net (code "10") (name "Net-(C229-Pad2)") (class "Default")
      (node (ref "C229") (pin "2") (pinfunction "2_2") (pintype "passive"))
      (node (ref "R117") (pin "1") (pinfunction "1_1") (pintype "passive"))
    )
    (net (code "11") (name "Net-(C230-Pad1)") (class "Default")
      (node (ref "C230") (pin "1") (pinfunction "1_1") (pintype "passive"))
      (node (ref "R119") (pin "2") (pinfunction "2_2") (pintype "passive"))
    )
    (net (code "12") (name "Net-(C230-Pad2)") (class "Default")
      (node (ref "C230") (pin "2") (pinfunction "2_2") (pintype "passive"))
      (node (ref "T2") (pin "6") (pintype "passive"))
    )
    (net (code "13") (name "Net-(C233-Pad2)") (class "Default")
      (node (ref "C233") (pin "2") (pinfunction "2_2") (pintype "passive"))
      (node (ref "R127") (pin "1") (pinfunction "1_1") (pintype "passive"))
    )
    (net (code "14") (name "Net-(C235-Pad2)") (class "Default")
      (node (ref "C235") (pin "2") (pinfunction "2_2") (pintype "passive"))
      (node (ref "R136") (pin "1") (pinfunction "1_1") (pintype "passive"))
    )
    (net (code "15") (name "Net-(D11-A)") (class "Default")
      (node (ref "D11") (pin "2") (pinfunction "A_2") (pintype "passive"))
      (node (ref "T1") (pin "5") (pintype "passive"))
      (node (ref "U13") (pin "5") (pintype "passive"))
      (node (ref "U13") (pin "6") (pintype "passive"))
      (node (ref "U13") (pin "7") (pintype "passive"))
      (node (ref "U13") (pin "8") (pintype "passive"))
    )
    (net (code "16") (name "Net-(D11-K)") (class "Default")
      (node (ref "C218") (pin "1") (pinfunction "1_1") (pintype "passive"))
      (node (ref "D11") (pin "1") (pinfunction "K_1") (pintype "passive"))
      (node (ref "R113") (pin "1") (pinfunction "1_1") (pintype "passive"))
    )
    (net (code "17") (name "Net-(D12-A)") (class "Default")
      (node (ref "D12") (pin "2") (pinfunction "A_2") (pintype "passive"))
      (node (ref "T1") (pin "2") (pintype "passive"))
    )
    (net (code "18") (name "Net-(D12-K)") (class "Default")
      (node (ref "C228") (pin "2") (pinfunction "2_2") (pintype "passive"))
      (node (ref "D12") (pin "1") (pinfunction "K_1") (pintype "passive"))
      (node (ref "R141") (pin "1") (pinfunction "1_1") (pintype "passive"))
      (node (ref "U11") (pin "6") (pinfunction "VC_6") (pintype "passive"))
    )
    (net (code "19") (name "Net-(D13-A)") (class "Default")
      (node (ref "D13") (pin "2") (pinfunction "A_2") (pintype "passive"))
      (node (ref "D15") (pin "1") (pinfunction "K_1") (pintype "passive"))
      (node (ref "R117") (pin "2") (pinfunction "2_2") (pintype "passive"))
      (node (ref "R118") (pin "2") (pinfunction "2_2") (pintype "passive"))
      (node (ref "U10") (pin "1") (pintype "passive"))
    )
    (net (code "20") (name "Net-(D13-K)") (class "Default")
      (node (ref "D13") (pin "1") (pinfunction "K_1") (pintype "passive"))
      (node (ref "R116") (pin "1") (pinfunction "1_1") (pintype "passive"))
      (node (ref "U10") (pin "2") (pintype "passive"))
    )
    (net (code "21") (name "Net-(D14-A)") (class "Default")
      (node (ref "D14") (pin "2") (pinfunction "A_2") (pintype "passive"))
      (node (ref "D17") (pin "1") (pinfunction "K_1") (pintype "passive"))
      (node (ref "LD3") (pin "2") (pinfunction "A_2") (pintype "passive"))
      (node (ref "R125") (pin "2") (pinfunction "2_2") (pintype "passive"))
      (node (ref "R129") (pin "2") (pinfunction "2_2") (pintype "passive"))
      (node (ref "R133") (pin "2") (pinfunction "2_2") (pintype "passive"))
    )
    (net (code "22") (name "Net-(D16-A)") (class "Default")
      (node (ref "D16") (pin "2") (pinfunction "A_2") (pintype "passive"))
      (node (ref "R128") (pin "2") (pinfunction "2_2") (pintype "passive"))
      (node (ref "U13") (pin "4") (pintype "passive"))
    )
    (net (code "23") (name "Net-(D16-K)") (class "Default")
      (node (ref "D16") (pin "1") (pinfunction "K_1") (pintype "passive"))
      (node (ref "R128") (pin "1") (pinfunction "1_1") (pintype "passive"))
      (node (ref "R132") (pin "2") (pinfunction "2_2") (pintype "passive"))
      (node (ref "U11") (pin "5") (pinfunction "GAT1_5") (pintype "passive"))
    )
    (net (code "24") (name "Net-(D17-A)") (class "Default")
      (node (ref "C238") (pin "2") (pinfunction "2_2") (pintype "passive"))
      (node (ref "D17") (pin "2") (pinfunction "A_2") (pintype "passive"))
      (node (ref "D18") (pin "1") (pinfunction "K_1") (pintype "passive"))
      (node (ref "R133") (pin "1") (pinfunction "1_1") (pintype "passive"))
    )
    (net (code "25") (name "Net-(D18-A)") (class "Default")
      (node (ref "C232") (pin "1") (pinfunction "1_1") (pintype "passive"))
      (node (ref "C234") (pin "1") (pinfunction "1_1") (pintype "passive"))
      (node (ref "C235") (pin "1") (pinfunction "1_1") (pintype "passive"))
      (node (ref "D18") (pin "2") (pinfunction "A_2") (pintype "passive"))
      (node (ref "R130") (pin "1") (pinfunction "1_1") (pintype "passive"))
      (node (ref "U14") (pin "3") (pinfunction "CATHODE_3") (pintype "passive"))
    )
    (net (code "26") (name "Net-(LD2-A)") (class "Default")
      (node (ref "LD2") (pin "2") (pinfunction "A_2") (pintype "passive"))
      (node (ref "R114") (pin "1") (pinfunction "1_1") (pintype "passive"))
    )
    (net (code "27") (name "Net-(LD3-K)") (class "Default")
      (node (ref "LD3") (pin "1") (pinfunction "K_1") (pintype "passive"))
      (node (ref "R142") (pin "1") (pinfunction "1_1") (pintype "passive"))
    )
    (net (code "28") (name "Net-(R116-Pad2)") (class "Default")
      (node (ref "R116") (pin "2") (pinfunction "2_2") (pintype "passive"))
      (node (ref "U9") (pin "4") (pintype "passive"))
    )
    (net (code "29") (name "Net-(R120-Pad1)") (class "Default")
      (node (ref "R120") (pin "1") (pinfunction "1_1") (pintype "passive"))
      (node (ref "T2") (pin "3") (pintype "passive"))
    )
    (net (code "30") (name "Net-(R121-Pad1)") (class "Default")
      (node (ref "R121") (pin "1") (pinfunction "1_1") (pintype "passive"))
      (node (ref "R123") (pin "2") (pinfunction "2_2") (pintype "passive"))
    )
    (net (code "31") (name "Net-(R124-Pad1)") (class "Default")
      (node (ref "R124") (pin "1") (pinfunction "1_1") (pintype "passive"))
      (node (ref "R131") (pin "1") (pinfunction "1_1") (pintype "passive"))
      (node (ref "U11") (pin "11") (pinfunction "VDD_11") (pintype "passive"))
      (node (ref "U11") (pin "12") (pinfunction "VDD_12") (pintype "passive"))
    )
    (net (code "32") (name "Net-(R134-Pad2)") (class "Default")
      (node (ref "R134") (pin "2") (pinfunction "2_2") (pintype "passive"))
      (node (ref "R137") (pin "2") (pinfunction "2_2") (pintype "passive"))
      (node (ref "R138") (pin "2") (pinfunction "2_2") (pintype "passive"))
      (node (ref "U13") (pin "1") (pintype "passive"))
      (node (ref "U13") (pin "2") (pintype "passive"))
      (node (ref "U13") (pin "3") (pintype "passive"))
    )
    (net (code "33") (name "Net-(U11-ARTN)") (class "Default")
      (node (ref "U11") (pin "17") (pinfunction "SA_17") (pintype "passive"))
      (node (ref "U11") (pin "4") (pinfunction "RTN1_4") (pintype "passive"))
      (node (ref "U11") (pin "8") (pinfunction "ARTN_8") (pintype "passive"))
      (node (ref "U11") (pin "9") (pinfunction "RTN2_9") (pintype "passive"))
    )
    (net (code "34") (name "Net-(U11-CLS)") (class "Default")
      (node (ref "R135") (pin "2") (pinfunction "2_2") (pintype "passive"))
      (node (ref "U11") (pin "15") (pinfunction "CLS_15") (pintype "passive"))
    )
    (net (code "35") (name "Net-(U11-CS)") (class "Default")
      (node (ref "C236") (pin "2") (pinfunction "2_2") (pintype "passive"))
      (node (ref "R134") (pin "1") (pinfunction "1_1") (pintype "passive"))
      (node (ref "U11") (pin "3") (pinfunction "CS_3") (pintype "passive"))
    )
    (net (code "36") (name "Net-(U11-CTL)") (class "Default")
      (node (ref "R126") (pin "2") (pinfunction "2_2") (pintype "passive"))
      (node (ref "R127") (pin "2") (pinfunction "2_2") (pintype "passive"))
      (node (ref "U11") (pin "1") (pinfunction "CTL_1") (pintype "passive"))
      (node (ref "U12") (pin "4") (pinfunction "Collector_4") (pintype "passive"))
    )
    (net (code "37") (name "Net-(U11-DET)") (class "Default")
      (node (ref "R131") (pin "2") (pinfunction "2_2") (pintype "passive"))
      (node (ref "U11") (pin "13") (pinfunction "DET_13") (pintype "passive"))
    )
    (net (code "38") (name "Net-(U11-DT)") (class "Default")
      (node (ref "R121") (pin "2") (pinfunction "2_2") (pintype "passive"))
      (node (ref "U11") (pin "18") (pinfunction "DT_18") (pintype "passive"))
    )
    (net (code "39") (name "Net-(U11-FRS)") (class "Default")
      (node (ref "R122") (pin "2") (pinfunction "2_2") (pintype "passive"))
      (node (ref "U11") (pin "19") (pinfunction "FRS_19") (pintype "passive"))
    )
    (net (code "40") (name "Net-(U11-GAT2)") (class "Default")
      (node (ref "R119") (pin "1") (pinfunction "1_1") (pintype "passive"))
      (node (ref "U11") (pin "7") (pinfunction "GAT2_7") (pintype "passive"))
    )
    (net (code "41") (name "Net-(U11-T2P)") (class "Default")
      (node (ref "U11") (pin "20") (pinfunction "T2P_20") (pintype "passive"))
      (node (ref "U15") (pin "2") (pinfunction "Cathode_2") (pintype "passive"))
    )
    (net (code "42") (name "Net-(U11-VB)") (class "Default")
      (node (ref "C237") (pin "2") (pinfunction "2_2") (pintype "passive"))
      (node (ref "R126") (pin "1") (pinfunction "1_1") (pintype "passive"))
      (node (ref "U11") (pin "2") (pinfunction "VB_2") (pintype "passive"))
    )
    (net (code "43") (name "Net-(U12-Anode)") (class "Default")
      (node (ref "C231") (pin "2") (pinfunction "2_2") (pintype "passive"))
      (node (ref "R125") (pin "1") (pinfunction "1_1") (pintype "passive"))
      (node (ref "U12") (pin "1") (pinfunction "Anode_1") (pintype "passive"))
    )
    (net (code "44") (name "Net-(U12-Cathode)") (class "Default")
      (node (ref "C232") (pin "2") (pinfunction "2_2") (pintype "passive"))
      (node (ref "R130") (pin "2") (pinfunction "2_2") (pintype "passive"))
      (node (ref "U12") (pin "2") (pinfunction "Cathode_2") (pintype "passive"))
    )
    (net (code "45") (name "Net-(U14-ANODE)") (class "Default")
      (node (ref "C238") (pin "1") (pinfunction "1_1") (pintype "passive"))
      (node (ref "R139") (pin "1") (pinfunction "1_1") (pintype "passive"))
      (node (ref "R140") (pin "1") (pinfunction "1_1") (pintype "passive"))
      (node (ref "U14") (pin "5") (pinfunction "ANODE_5") (pintype "passive"))
    )
    (net (code "46") (name "Net-(U14-REF)") (class "Default")
      (node (ref "C234") (pin "2") (pinfunction "2_2") (pintype "passive"))
      (node (ref "R129") (pin "1") (pinfunction "1_1") (pintype "passive"))
      (node (ref "R136") (pin "2") (pinfunction "2_2") (pintype "passive"))
      (node (ref "R139") (pin "2") (pinfunction "2_2") (pintype "passive"))
      (node (ref "R140") (pin "2") (pinfunction "2_2") (pintype "passive"))
      (node (ref "U14") (pin "4") (pinfunction "REF_4") (pintype "passive"))
    )
    (net (code "47") (name "Net-(U15-Anode)") (class "Default")
      (node (ref "R141") (pin "2") (pinfunction "2_2") (pintype "passive"))
      (node (ref "U15") (pin "1") (pinfunction "Anode_1") (pintype "passive"))
    )
    (net (code "48") (name "RTN") (class "Default")
      (node (ref "C214") (pin "2") (pinfunction "2_2") (pintype "passive"))
      (node (ref "C215") (pin "1") (pinfunction "1_1") (pintype "passive"))
      (node (ref "C216") (pin "1") (pinfunction "1_1") (pintype "passive"))
      (node (ref "C217") (pin "1") (pinfunction "1_1") (pintype "passive"))
      (node (ref "C228") (pin "1") (pinfunction "1_1") (pintype "passive"))
      (node (ref "C233") (pin "1") (pinfunction "1_1") (pintype "passive"))
      (node (ref "C236") (pin "1") (pinfunction "1_1") (pintype "passive"))
      (node (ref "C237") (pin "1") (pinfunction "1_1") (pintype "passive"))
      (node (ref "C239") (pin "1") (pinfunction "1_1") (pintype "passive"))
      (node (ref "R122") (pin "1") (pinfunction "1_1") (pintype "passive"))
      (node (ref "R123") (pin "1") (pinfunction "1_1") (pintype "passive"))
      (node (ref "R132") (pin "1") (pinfunction "1_1") (pintype "passive"))
      (node (ref "R137") (pin "1") (pinfunction "1_1") (pintype "passive"))
      (node (ref "R138") (pin "1") (pinfunction "1_1") (pintype "passive"))
      (node (ref "T1") (pin "1") (pintype "passive"))
      (node (ref "T2") (pin "4") (pintype "passive"))
      (node (ref "U12") (pin "3") (pinfunction "Emitter_3") (pintype "passive"))
    )
    (net (code "49") (name "VU_12V0_PoE") (class "Default")
      (node (ref "C220") (pin "1") (pinfunction "1_1") (pintype "passive"))
      (node (ref "C221") (pin "2") (pinfunction "2_2") (pintype "passive"))
      (node (ref "C226") (pin "2") (pinfunction "2_2") (pintype "passive"))
      (node (ref "C227") (pin "2") (pinfunction "2_2") (pintype "passive"))
      (node (ref "D14") (pin "1") (pinfunction "K_1") (pintype "passive"))
      (node (ref "L2") (pin "2") (pinfunction "2_2") (pintype "passive"))
      (node (ref "R114") (pin "2") (pinfunction "2_2") (pintype "passive"))
    )
    (net (code "50") (name "unconnected-(U11-DCCL-Pad16)") (class "Default")
      (node (ref "U11") (pin "16") (pinfunction "DCCL_16") (pintype "passive+no_connect"))
    )
    (net (code "51") (name "unconnected-(U14-NC-Pad1)") (class "Default")
      (node (ref "U14") (pin "1") (pinfunction "NC_1") (pintype "passive+no_connect"))
    )
    (net (code "52") (name "unconnected-(U14-NC-Pad2)") (class "Default")
      (node (ref "U14") (pin "2") (pinfunction "NC_2") (pintype "passive+no_connect"))
    )
  )
)
